# 23_LMS2_RX1_BB_ADC.net
KiCad netlist of a schematic drawn in Altium Designer
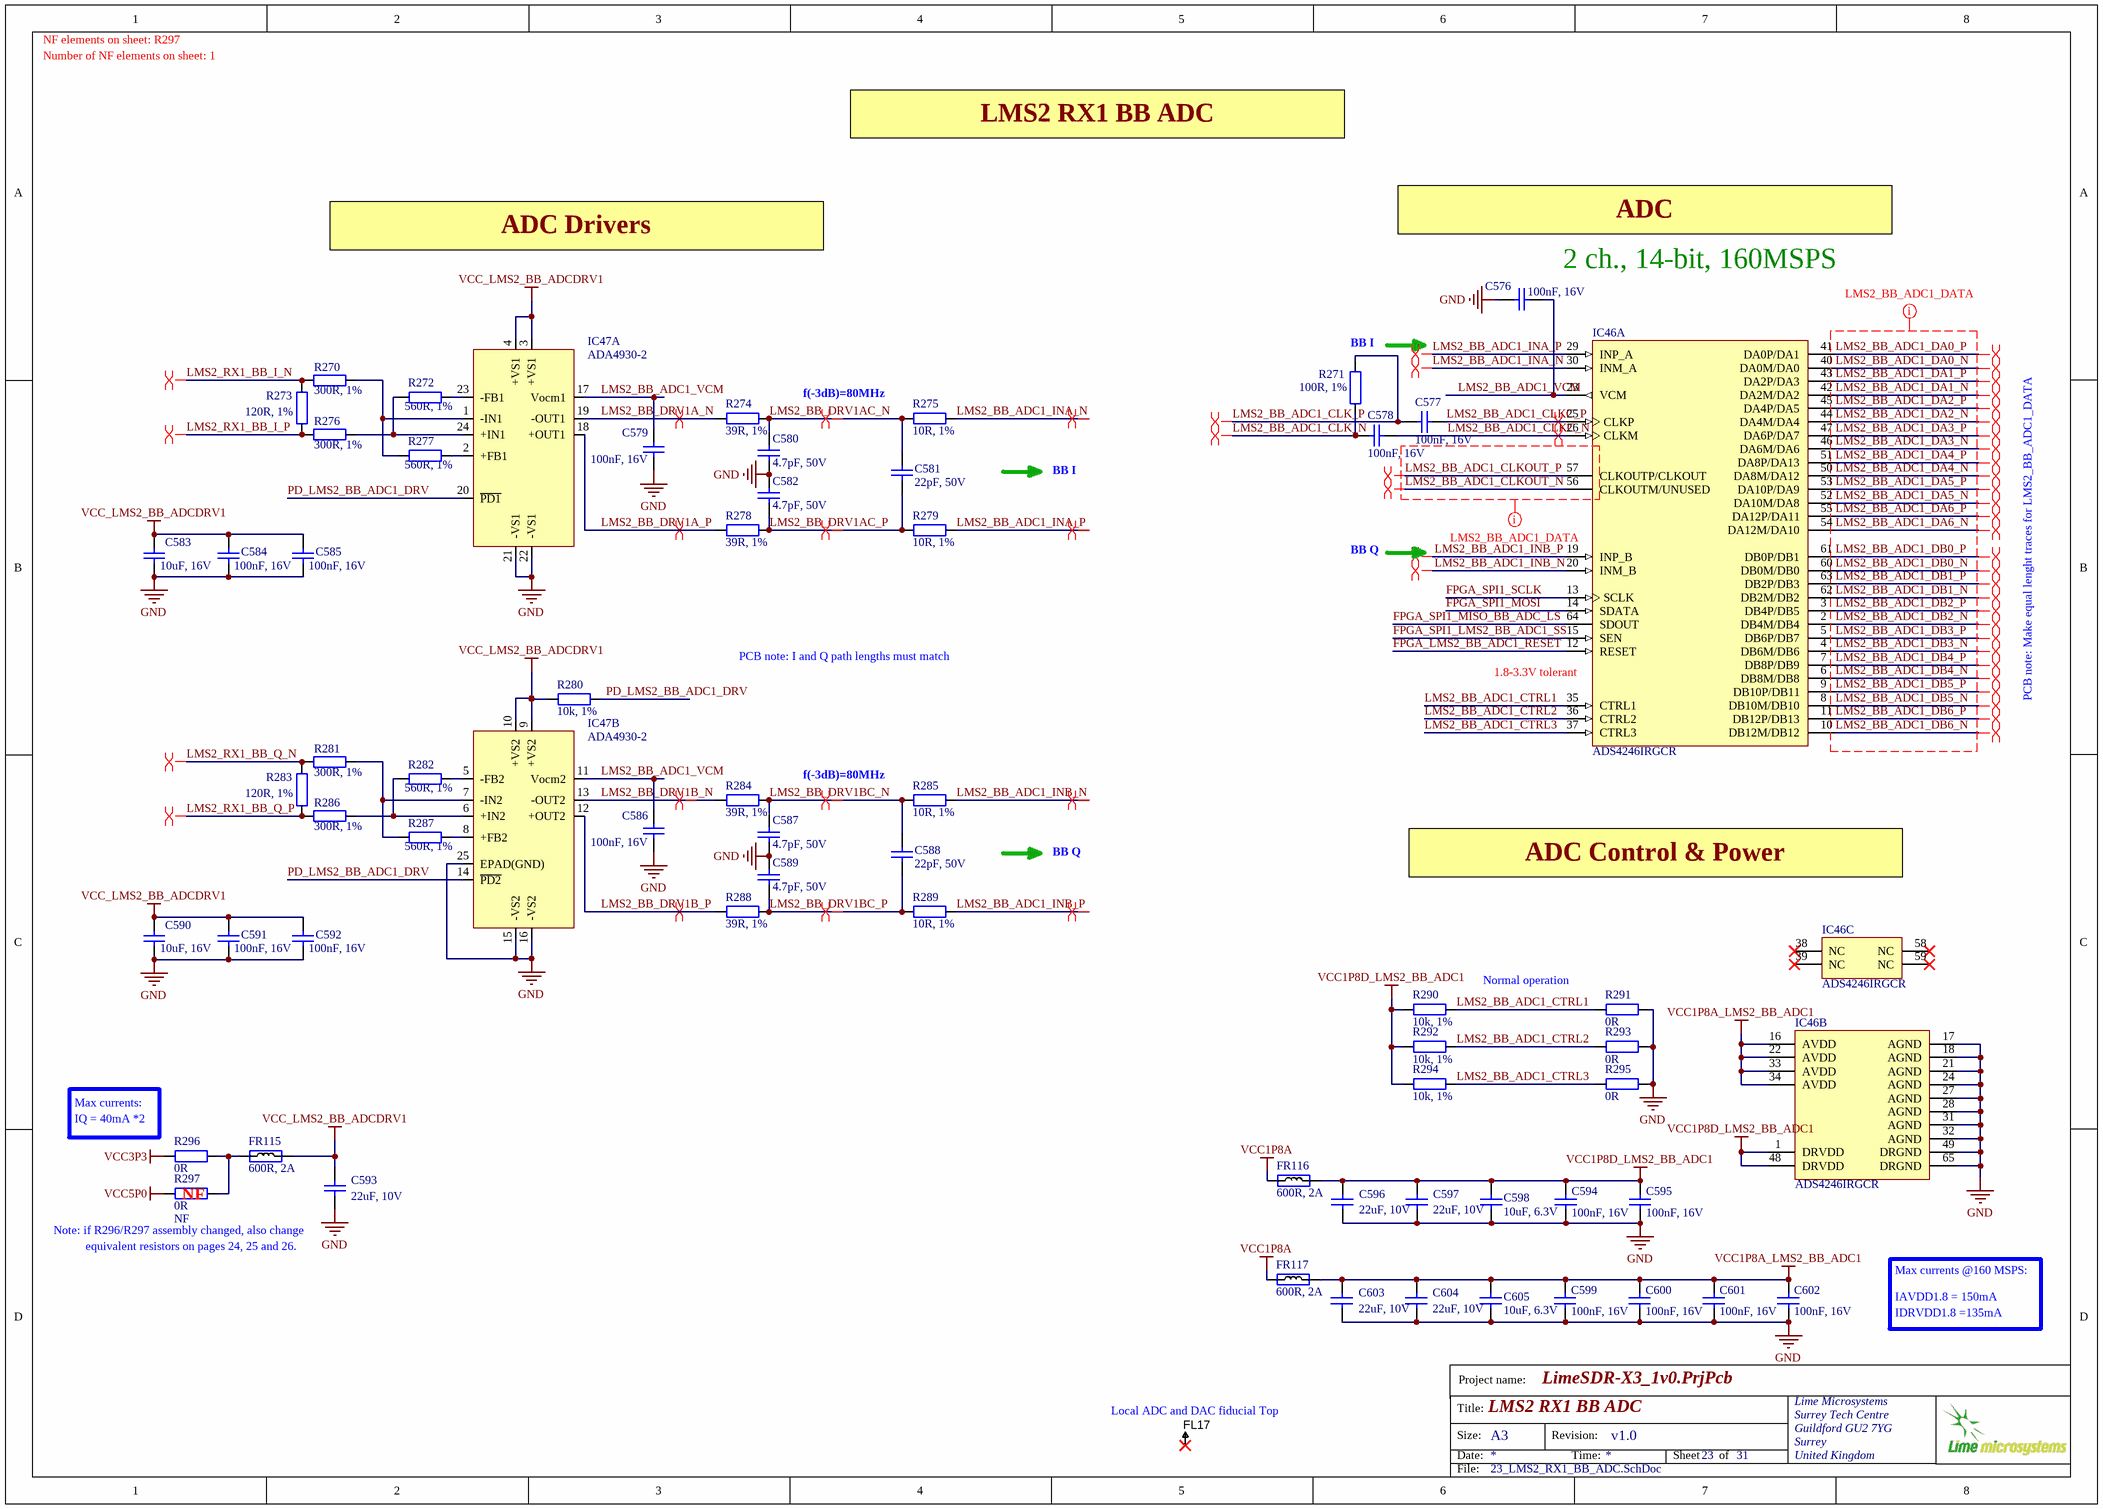
[diagram p0: 23_LMS2_RX1_BB_ADC.SchDoc]

(export (version "E")
  (design (tool "Eeschema 10.0.6"))
  (components
    (comp (ref "C576")
      (value "100nF, 16V")
      (footprint "CAP0402")
      (fields (field (name "TOLERANCE") "10 %") (field (name "MANUFACTURER") "Murata Electronics"))
      (libsource (lib "") (part "Cap_0603_3"))
    )
    (comp (ref "C577")
      (value "100nF, 16V")
      (footprint "CAP0402")
      (fields (field (name "TOLERANCE") "10 %") (field (name "MANUFACTURER") "Murata Electronics"))
      (libsource (lib "") (part "Cap_0603_3"))
    )
    (comp (ref "C578")
      (value "100nF, 16V")
      (footprint "CAP0402")
      (fields (field (name "TOLERANCE") "10 %") (field (name "MANUFACTURER") "Murata Electronics"))
      (libsource (lib "") (part "Cap_0603_4"))
    )
    (comp (ref "C579")
      (value "100nF, 16V")
      (footprint "CAP0402")
      (fields (field (name "TOLERANCE") "10 %") (field (name "MANUFACTURER") "Murata Electronics"))
      (libsource (lib "") (part "Cap_0603_4"))
    )
    (comp (ref "C580")
      (value "4.7pF, 50V")
      (footprint "CAP0402")
      (fields (field (name "MANUFACTURER") "MURATA"))
      (libsource (lib "") (part "Cap_0402_1"))
    )
    (comp (ref "C581")
      (value "22pF, 50V")
      (footprint "CAP0402")
      (fields (field (name "TOLERANCE") "±5%") (field (name "MANUFACTURER") "Yageo"))
      (libsource (lib "LimeMicroAltiumLib_schLib") (part "Cap_0402"))
    )
    (comp (ref "C582")
      (value "4.7pF, 50V")
      (footprint "CAP0402")
      (fields (field (name "MANUFACTURER") "MURATA"))
      (libsource (lib "") (part "Cap_0402_1"))
    )
    (comp (ref "C583")
      (value "10uF, 16V")
      (footprint "CAP0603")
      (fields (field (name "MANUFACTURER") "Yageo") (field (name "TOLERANCE") "±20%"))
      (libsource (lib "LimeMicroAltiumLib_schLib") (part "Cap_0603"))
    )
    (comp (ref "C584")
      (value "100nF, 16V")
      (footprint "CAP0402")
      (fields (field (name "TOLERANCE") "10 %") (field (name "MANUFACTURER") "Murata Electronics"))
      (libsource (lib "") (part "Cap_0603_4"))
    )
    (comp (ref "C585")
      (value "100nF, 16V")
      (footprint "CAP0402")
      (fields (field (name "TOLERANCE") "10 %") (field (name "MANUFACTURER") "Murata Electronics"))
      (libsource (lib "") (part "Cap_0603_4"))
    )
    (comp (ref "C586")
      (value "100nF, 16V")
      (footprint "CAP0402")
      (fields (field (name "TOLERANCE") "10 %") (field (name "MANUFACTURER") "Murata Electronics"))
      (libsource (lib "") (part "Cap_0603_5"))
    )
    (comp (ref "C587")
      (value "4.7pF, 50V")
      (footprint "CAP0402")
      (fields (field (name "MANUFACTURER") "MURATA"))
      (libsource (lib "") (part "Cap_0402_1"))
    )
    (comp (ref "C588")
      (value "22pF, 50V")
      (footprint "CAP0402")
      (fields (field (name "TOLERANCE") "±5%") (field (name "MANUFACTURER") "Yageo"))
      (libsource (lib "LimeMicroAltiumLib_schLib") (part "Cap_0402"))
    )
    (comp (ref "C589")
      (value "4.7pF, 50V")
      (footprint "CAP0402")
      (fields (field (name "MANUFACTURER") "MURATA"))
      (libsource (lib "") (part "Cap_0402_1"))
    )
    (comp (ref "C590")
      (value "10uF, 16V")
      (footprint "CAP0603")
      (fields (field (name "MANUFACTURER") "Yageo") (field (name "TOLERANCE") "±20%"))
      (libsource (lib "LimeMicroAltiumLib_schLib") (part "Cap_0603"))
    )
    (comp (ref "C591")
      (value "100nF, 16V")
      (footprint "CAP0402")
      (fields (field (name "TOLERANCE") "10 %") (field (name "MANUFACTURER") "Murata Electronics"))
      (libsource (lib "") (part "Cap_0603_4"))
    )
    (comp (ref "C592")
      (value "100nF, 16V")
      (footprint "CAP0402")
      (fields (field (name "TOLERANCE") "10 %") (field (name "MANUFACTURER") "Murata Electronics"))
      (libsource (lib "") (part "Cap_0603_4"))
    )
    (comp (ref "C593")
      (value "22uF, 10V")
      (footprint "CAP0603")
      (fields (field (name "TOLERANCE") "20 %") (field (name "MANUFACTURER") "TDK Corporation"))
      (libsource (lib "") (part "Cap_0603_6"))
    )
    (comp (ref "C594")
      (value "100nF, 16V")
      (footprint "CAP0402")
      (fields (field (name "TOLERANCE") "10 %") (field (name "MANUFACTURER") "Murata Electronics"))
      (libsource (lib "") (part "Cap_0603_1"))
    )
    (comp (ref "C595")
      (value "100nF, 16V")
      (footprint "CAP0402")
      (fields (field (name "TOLERANCE") "10 %") (field (name "MANUFACTURER") "Murata Electronics"))
      (libsource (lib "") (part "Cap_0603_1"))
    )
    (comp (ref "C596")
      (value "22uF, 10V")
      (footprint "CAP0603")
      (fields (field (name "TOLERANCE") "20 %") (field (name "MANUFACTURER") "TDK Corporation"))
      (libsource (lib "") (part "Cap_0603_1"))
    )
    (comp (ref "C597")
      (value "22uF, 10V")
      (footprint "CAP0603")
      (fields (field (name "TOLERANCE") "20 %") (field (name "MANUFACTURER") "TDK Corporation"))
      (libsource (lib "") (part "Cap_0603_1"))
    )
    (comp (ref "C598")
      (value "10uF, 6.3V")
      (footprint "CAP0603")
      (fields (field (name "TOLERANCE") "±20%") (field (name "MANUFACTURER") "Yageo"))
      (libsource (lib "") (part "Cap_0603_7"))
    )
    (comp (ref "C599")
      (value "100nF, 16V")
      (footprint "CAP0402")
      (fields (field (name "TOLERANCE") "10 %") (field (name "MANUFACTURER") "Murata Electronics"))
      (libsource (lib "LimeFPGAboard_schLib") (part "Cap_0603"))
    )
    (comp (ref "C600")
      (value "100nF, 16V")
      (footprint "CAP0402")
      (fields (field (name "TOLERANCE") "10 %") (field (name "MANUFACTURER") "Murata Electronics"))
      (libsource (lib "LimeFPGAboard_schLib") (part "Cap_0603"))
    )
    (comp (ref "C601")
      (value "100nF, 16V")
      (footprint "CAP0402")
      (fields (field (name "TOLERANCE") "10 %") (field (name "MANUFACTURER") "Murata Electronics"))
      (libsource (lib "LimeFPGAboard_schLib") (part "Cap_0603"))
    )
    (comp (ref "C602")
      (value "100nF, 16V")
      (footprint "CAP0402")
      (fields (field (name "TOLERANCE") "10 %") (field (name "MANUFACTURER") "Murata Electronics"))
      (libsource (lib "LimeFPGAboard_schLib") (part "Cap_0603"))
    )
    (comp (ref "C603")
      (value "22uF, 10V")
      (footprint "CAP0603")
      (fields (field (name "TOLERANCE") "20 %") (field (name "MANUFACTURER") "TDK Corporation"))
      (libsource (lib "LimeFPGAboard_schLib") (part "Cap_0603"))
    )
    (comp (ref "C604")
      (value "22uF, 10V")
      (footprint "CAP0603")
      (fields (field (name "TOLERANCE") "20 %") (field (name "MANUFACTURER") "TDK Corporation"))
      (libsource (lib "LimeFPGAboard_schLib") (part "Cap_0603"))
    )
    (comp (ref "C605")
      (value "10uF, 6.3V")
      (footprint "CAP0603")
      (fields (field (name "TOLERANCE") "±20%") (field (name "MANUFACTURER") "Yageo"))
      (libsource (lib "") (part "Cap_0603_2"))
    )
    (comp (ref "FL17")
      (value "Fiducial")
      (footprint "Fiducial_local")
      (libsource (lib "LimeMicroAltiumLib_schLib") (part "Fiducial"))
    )
    (comp (ref "FR115")
      (value "600R, 2A")
      (footprint "RES0805")
      (fields (field (name "MANUFACTURER") "TDK Corporation"))
      (libsource (lib "LimeMicroAltiumLib_schLib") (part "Ferrite"))
    )
    (comp (ref "FR116")
      (value "600R, 2A")
      (footprint "RES0805")
      (fields (field (name "MANUFACTURER") "TDK Corporation"))
      (libsource (lib "LimeFPGAboard_schLib") (part "Ferrite"))
    )
    (comp (ref "FR117")
      (value "600R, 2A")
      (footprint "RES0805")
      (fields (field (name "MANUFACTURER") "TDK Corporation"))
      (libsource (lib "LimeFPGAboard_schLib") (part "Ferrite"))
    )
    (comp (ref "IC46")
      (value "ADS4246IRGCR")
      (footprint "TI-RGC64-7400X7400TP_V")
      (description "14-Bit 160 MSPS Dual Low Power ADC, -40 to 85 degC, 64-pin QFN (RGC64), Green (RoHS & no Sb/Br)")
      (fields (field (name "MANUFACTURER") "Texas Instruments"))
      (libsource (lib "") (part "ADS4246IRGCR_1"))
    )
    (comp (ref "IC47")
      (value "ADA4930-2")
      (footprint "ADA4930-2_LFCSP-24")
      (fields (field (name "MANUFACTURER") "Analog Devices Inc."))
      (libsource (lib "") (part "ADA4930-2_1"))
    )
    (comp (ref "R270")
      (value "300R, 1%")
      (footprint "RES0402")
      (fields (field (name "TOLERANCE") "±1%") (field (name "MANUFACTURER") "Vishay Dale"))
      (libsource (lib "") (part "Res_0402_1"))
    )
    (comp (ref "R271")
      (value "100R, 1%")
      (footprint "RES0402")
      (fields (field (name "TOLERANCE") "±1%") (field (name "MANUFACTURER") "Stackpole Electronics Inc."))
      (libsource (lib "") (part "Res_0402_1"))
    )
    (comp (ref "R272")
      (value "560R, 1%")
      (footprint "RES0402")
      (fields (field (name "TOLERANCE") "±1%") (field (name "MANUFACTURER") "Vishay Dale"))
      (libsource (lib "") (part "Res_0402_1"))
    )
    (comp (ref "R273")
      (value "120R, 1%")
      (footprint "RES0402")
      (fields (field (name "MANUFACTURER") "Yageo") (field (name "TOLERANCE") "1%"))
      (libsource (lib "LimeFPGAboard_schLib") (part "Res_0402"))
    )
    (comp (ref "R274")
      (value "39R, 1%")
      (footprint "RES0402")
      (fields (field (name "MANUFACTURER") "Yageo") (field (name "TOLERANCE") "1%"))
      (libsource (lib "LimeMicroAltiumLib_schLib") (part "Res_0402"))
    )
    (comp (ref "R275")
      (value "10R, 1%")
      (footprint "RES0402")
      (fields (field (name "TOLERANCE") "1%"))
      (libsource (lib "LimeMicroAltiumLib_schLib") (part "Res_0402"))
    )
    (comp (ref "R276")
      (value "300R, 1%")
      (footprint "RES0402")
      (fields (field (name "TOLERANCE") "±1%") (field (name "MANUFACTURER") "Vishay Dale"))
      (libsource (lib "") (part "Res_0402_1"))
    )
    (comp (ref "R277")
      (value "560R, 1%")
      (footprint "RES0402")
      (fields (field (name "TOLERANCE") "±1%") (field (name "MANUFACTURER") "Vishay Dale"))
      (libsource (lib "") (part "Res_0402_1"))
    )
    (comp (ref "R278")
      (value "39R, 1%")
      (footprint "RES0402")
      (fields (field (name "MANUFACTURER") "Yageo") (field (name "TOLERANCE") "1%"))
      (libsource (lib "LimeMicroAltiumLib_schLib") (part "Res_0402"))
    )
    (comp (ref "R279")
      (value "10R, 1%")
      (footprint "RES0402")
      (fields (field (name "TOLERANCE") "1%"))
      (libsource (lib "LimeMicroAltiumLib_schLib") (part "Res_0402"))
    )
    (comp (ref "R280")
      (value "10k, 1%")
      (footprint "RES0402")
      (fields (field (name "MANUFACTURER") "Yageo") (field (name "TOLERANCE") "±1%"))
      (libsource (lib "LimeMicroAltiumLib_schLib") (part "Res_0402"))
    )
    (comp (ref "R281")
      (value "300R, 1%")
      (footprint "RES0402")
      (fields (field (name "TOLERANCE") "±1%") (field (name "MANUFACTURER") "Vishay Dale"))
      (libsource (lib "") (part "Res_0402_1"))
    )
    (comp (ref "R282")
      (value "560R, 1%")
      (footprint "RES0402")
      (fields (field (name "TOLERANCE") "±1%") (field (name "MANUFACTURER") "Vishay Dale"))
      (libsource (lib "") (part "Res_0402_1"))
    )
    (comp (ref "R283")
      (value "120R, 1%")
      (footprint "RES0402")
      (fields (field (name "MANUFACTURER") "Yageo") (field (name "TOLERANCE") "1%"))
      (libsource (lib "LimeFPGAboard_schLib") (part "Res_0402"))
    )
    (comp (ref "R284")
      (value "39R, 1%")
      (footprint "RES0402")
      (fields (field (name "MANUFACTURER") "Yageo") (field (name "TOLERANCE") "1%"))
      (libsource (lib "LimeMicroAltiumLib_schLib") (part "Res_0402"))
    )
    (comp (ref "R285")
      (value "10R, 1%")
      (footprint "RES0402")
      (fields (field (name "TOLERANCE") "1%"))
      (libsource (lib "LimeMicroAltiumLib_schLib") (part "Res_0402"))
    )
    (comp (ref "R286")
      (value "300R, 1%")
      (footprint "RES0402")
      (fields (field (name "TOLERANCE") "±1%") (field (name "MANUFACTURER") "Vishay Dale"))
      (libsource (lib "") (part "Res_0402_1"))
    )
    (comp (ref "R287")
      (value "560R, 1%")
      (footprint "RES0402")
      (fields (field (name "TOLERANCE") "±1%") (field (name "MANUFACTURER") "Vishay Dale"))
      (libsource (lib "") (part "Res_0402_1"))
    )
    (comp (ref "R288")
      (value "39R, 1%")
      (footprint "RES0402")
      (fields (field (name "MANUFACTURER") "Yageo") (field (name "TOLERANCE") "1%"))
      (libsource (lib "LimeMicroAltiumLib_schLib") (part "Res_0402"))
    )
    (comp (ref "R289")
      (value "10R, 1%")
      (footprint "RES0402")
      (fields (field (name "TOLERANCE") "1%"))
      (libsource (lib "LimeMicroAltiumLib_schLib") (part "Res_0402"))
    )
    (comp (ref "R290")
      (value "10k, 1%")
      (footprint "RES0402")
      (fields (field (name "MANUFACTURER") "Yageo") (field (name "TOLERANCE") "±1%"))
      (libsource (lib "LimeMicroAltiumLib_schLib") (part "Res_0402"))
    )
    (comp (ref "R291")
      (value "0R")
      (footprint "RES0402")
      (fields (field (name "MANUFACTURER") "Yageo"))
      (libsource (lib "") (part "Res_0402_1"))
    )
    (comp (ref "R292")
      (value "10k, 1%")
      (footprint "RES0402")
      (fields (field (name "MANUFACTURER") "Yageo") (field (name "TOLERANCE") "±1%"))
      (libsource (lib "LimeMicroAltiumLib_schLib") (part "Res_0402"))
    )
    (comp (ref "R293")
      (value "0R")
      (footprint "RES0402")
      (fields (field (name "MANUFACTURER") "Yageo"))
      (libsource (lib "") (part "Res_0402_1"))
    )
    (comp (ref "R294")
      (value "10k, 1%")
      (footprint "RES0402")
      (fields (field (name "MANUFACTURER") "Yageo") (field (name "TOLERANCE") "±1%"))
      (libsource (lib "LimeMicroAltiumLib_schLib") (part "Res_0402"))
    )
    (comp (ref "R295")
      (value "0R")
      (footprint "RES0402")
      (fields (field (name "MANUFACTURER") "Yageo"))
      (libsource (lib "") (part "Res_0402_1"))
    )
    (comp (ref "R296")
      (value "0R")
      (footprint "RES0402")
      (fields (field (name "MANUFACTURER") "Yageo") (field (name "TOLERANCE") "Jumper"))
      (libsource (lib "LimeMicroAltiumLib_schLib") (part "Res_0402"))
    )
    (comp (ref "R297")
      (value "0R")
      (footprint "RES0402")
      (fields
        (field (name "ASSEMBLY INFO") "NF")
        (field (name "MANUFACTURER") "Yageo")
        (field (name "TOLERANCE") "Jumper")
      )
      (libsource (lib "LimeMicroAltiumLib_schLib") (part "Res_0402"))
    )
  )
  (nets
    (net (code "1") (name "/FPGA_LMS2_BB_ADC1_RESET") (class "Default")
      (node (ref "IC46") (pin "12") (pinfunction "RESET_12") (pintype "input"))
    )
    (net (code "2") (name "/FPGA_SPI1_LMS2_BB_ADC1_SS") (class "Default")
      (node (ref "IC46") (pin "15") (pinfunction "SEN_15") (pintype "input"))
    )
    (net (code "3") (name "/FPGA_SPI1_MISO_BB_ADC_LS") (class "Default")
      (node (ref "IC46") (pin "64") (pinfunction "SDOUT_64") (pintype "tri_state"))
    )
    (net (code "4") (name "/FPGA_SPI1_MOSI") (class "Default")
      (node (ref "IC46") (pin "14") (pinfunction "SDATA_14") (pintype "input"))
    )
    (net (code "5") (name "/FPGA_SPI1_SCLK") (class "Default")
      (node (ref "IC46") (pin "13") (pinfunction "SCLK_13") (pintype "input"))
    )
    (net (code "6") (name "/LMS2_BB_ADC1_CLKC_N") (class "Default")
      (node (ref "C578") (pin "1") (pinfunction "1_1") (pintype "passive"))
      (node (ref "IC46") (pin "26") (pinfunction "CLKM_26") (pintype "input"))
    )
    (net (code "7") (name "/LMS2_BB_ADC1_CLKC_P") (class "Default")
      (node (ref "C577") (pin "1") (pinfunction "1_1") (pintype "passive"))
      (node (ref "IC46") (pin "25") (pinfunction "CLKP_25") (pintype "input"))
    )
    (net (code "8") (name "/LMS2_BB_ADC1_CLKOUT_N") (class "Default")
      (node (ref "IC46") (pin "56") (pinfunction "CLKOUTM/UNUSED_56") (pintype "tri_state"))
    )
    (net (code "9") (name "/LMS2_BB_ADC1_CLKOUT_P") (class "Default")
      (node (ref "IC46") (pin "57") (pinfunction "CLKOUTP/CLKOUT_57") (pintype "tri_state"))
    )
    (net (code "10") (name "/LMS2_BB_ADC1_CLK_N") (class "Default")
      (node (ref "C578") (pin "2") (pinfunction "2_2") (pintype "passive"))
      (node (ref "R271") (pin "1") (pinfunction "1_1") (pintype "passive"))
    )
    (net (code "11") (name "/LMS2_BB_ADC1_CLK_P") (class "Default")
      (node (ref "C577") (pin "2") (pinfunction "2_2") (pintype "passive"))
      (node (ref "R271") (pin "2") (pinfunction "2_2") (pintype "passive"))
    )
    (net (code "12") (name "/LMS2_BB_ADC1_CTRL1") (class "Default")
      (node (ref "IC46") (pin "35") (pinfunction "CTRL1_35") (pintype "input"))
      (node (ref "R290") (pin "1") (pinfunction "1_1") (pintype "passive"))
      (node (ref "R291") (pin "2") (pinfunction "2_2") (pintype "passive"))
    )
    (net (code "13") (name "/LMS2_BB_ADC1_CTRL2") (class "Default")
      (node (ref "IC46") (pin "36") (pinfunction "CTRL2_36") (pintype "input"))
      (node (ref "R292") (pin "1") (pinfunction "1_1") (pintype "passive"))
      (node (ref "R293") (pin "2") (pinfunction "2_2") (pintype "passive"))
    )
    (net (code "14") (name "/LMS2_BB_ADC1_CTRL3") (class "Default")
      (node (ref "IC46") (pin "37") (pinfunction "CTRL3_37") (pintype "input"))
      (node (ref "R294") (pin "1") (pinfunction "1_1") (pintype "passive"))
      (node (ref "R295") (pin "2") (pinfunction "2_2") (pintype "passive"))
    )
    (net (code "15") (name "/LMS2_BB_ADC1_DA0_N") (class "Default")
      (node (ref "IC46") (pin "40") (pinfunction "DA0M/DA0_40") (pintype "tri_state"))
    )
    (net (code "16") (name "/LMS2_BB_ADC1_DA0_P") (class "Default")
      (node (ref "IC46") (pin "41") (pinfunction "DA0P/DA1_41") (pintype "tri_state"))
    )
    (net (code "17") (name "/LMS2_BB_ADC1_DA1_N") (class "Default")
      (node (ref "IC46") (pin "42") (pinfunction "DA2M/DA2_42") (pintype "tri_state"))
    )
    (net (code "18") (name "/LMS2_BB_ADC1_DA1_P") (class "Default")
      (node (ref "IC46") (pin "43") (pinfunction "DA2P/DA3_43") (pintype "tri_state"))
    )
    (net (code "19") (name "/LMS2_BB_ADC1_DA2_N") (class "Default")
      (node (ref "IC46") (pin "44") (pinfunction "DA4M/DA4_44") (pintype "tri_state"))
    )
    (net (code "20") (name "/LMS2_BB_ADC1_DA2_P") (class "Default")
      (node (ref "IC46") (pin "45") (pinfunction "DA4P/DA5_45") (pintype "tri_state"))
    )
    (net (code "21") (name "/LMS2_BB_ADC1_DA3_N") (class "Default")
      (node (ref "IC46") (pin "46") (pinfunction "DA6M/DA6_46") (pintype "tri_state"))
    )
    (net (code "22") (name "/LMS2_BB_ADC1_DA3_P") (class "Default")
      (node (ref "IC46") (pin "47") (pinfunction "DA6P/DA7_47") (pintype "tri_state"))
    )
    (net (code "23") (name "/LMS2_BB_ADC1_DA4_N") (class "Default")
      (node (ref "IC46") (pin "50") (pinfunction "DA8M/DA12_50") (pintype "tri_state"))
    )
    (net (code "24") (name "/LMS2_BB_ADC1_DA4_P") (class "Default")
      (node (ref "IC46") (pin "51") (pinfunction "DA8P/DA13_51") (pintype "tri_state"))
    )
    (net (code "25") (name "/LMS2_BB_ADC1_DA5_N") (class "Default")
      (node (ref "IC46") (pin "52") (pinfunction "DA10M/DA8_52") (pintype "tri_state"))
    )
    (net (code "26") (name "/LMS2_BB_ADC1_DA5_P") (class "Default")
      (node (ref "IC46") (pin "53") (pinfunction "DA10P/DA9_53") (pintype "tri_state"))
    )
    (net (code "27") (name "/LMS2_BB_ADC1_DA6_N") (class "Default")
      (node (ref "IC46") (pin "54") (pinfunction "DA12M/DA10_54") (pintype "tri_state"))
    )
    (net (code "28") (name "/LMS2_BB_ADC1_DA6_P") (class "Default")
      (node (ref "IC46") (pin "55") (pinfunction "DA12P/DA11_55") (pintype "tri_state"))
    )
    (net (code "29") (name "/LMS2_BB_ADC1_DB0_N") (class "Default")
      (node (ref "IC46") (pin "60") (pinfunction "DB0M/DB0_60") (pintype "tri_state"))
    )
    (net (code "30") (name "/LMS2_BB_ADC1_DB0_P") (class "Default")
      (node (ref "IC46") (pin "61") (pinfunction "DB0P/DB1_61") (pintype "tri_state"))
    )
    (net (code "31") (name "/LMS2_BB_ADC1_DB1_N") (class "Default")
      (node (ref "IC46") (pin "62") (pinfunction "DB2M/DB2_62") (pintype "tri_state"))
    )
    (net (code "32") (name "/LMS2_BB_ADC1_DB1_P") (class "Default")
      (node (ref "IC46") (pin "63") (pinfunction "DB2P/DB3_63") (pintype "tri_state"))
    )
    (net (code "33") (name "/LMS2_BB_ADC1_DB2_N") (class "Default")
      (node (ref "IC46") (pin "2") (pinfunction "DB4M/DB4_2") (pintype "tri_state"))
    )
    (net (code "34") (name "/LMS2_BB_ADC1_DB2_P") (class "Default")
      (node (ref "IC46") (pin "3") (pinfunction "DB4P/DB5_3") (pintype "tri_state"))
    )
    (net (code "35") (name "/LMS2_BB_ADC1_DB3_N") (class "Default")
      (node (ref "IC46") (pin "4") (pinfunction "DB6M/DB6_4") (pintype "tri_state"))
    )
    (net (code "36") (name "/LMS2_BB_ADC1_DB3_P") (class "Default")
      (node (ref "IC46") (pin "5") (pinfunction "DB6P/DB7_5") (pintype "tri_state"))
    )
    (net (code "37") (name "/LMS2_BB_ADC1_DB4_N") (class "Default")
      (node (ref "IC46") (pin "6") (pinfunction "DB8M/DB8_6") (pintype "tri_state"))
    )
    (net (code "38") (name "/LMS2_BB_ADC1_DB4_P") (class "Default")
      (node (ref "IC46") (pin "7") (pinfunction "DB8P/DB9_7") (pintype "tri_state"))
    )
    (net (code "39") (name "/LMS2_BB_ADC1_DB5_N") (class "Default")
      (node (ref "IC46") (pin "8") (pinfunction "DB10M/DB10_8") (pintype "tri_state"))
    )
    (net (code "40") (name "/LMS2_BB_ADC1_DB5_P") (class "Default")
      (node (ref "IC46") (pin "9") (pinfunction "DB10P/DB11_9") (pintype "tri_state"))
    )
    (net (code "41") (name "/LMS2_BB_ADC1_DB6_N") (class "Default")
      (node (ref "IC46") (pin "10") (pinfunction "DB12M/DB12_10") (pintype "tri_state"))
    )
    (net (code "42") (name "/LMS2_BB_ADC1_DB6_P") (class "Default")
      (node (ref "IC46") (pin "11") (pinfunction "DB12P/DB13_11") (pintype "tri_state"))
    )
    (net (code "43") (name "/LMS2_BB_ADC1_INA_N") (class "Default")
      (node (ref "IC46") (pin "30") (pinfunction "INM_A_30") (pintype "input"))
      (node (ref "R275") (pin "1") (pinfunction "1_1") (pintype "passive"))
    )
    (net (code "44") (name "/LMS2_BB_ADC1_INA_P") (class "Default")
      (node (ref "IC46") (pin "29") (pinfunction "INP_A_29") (pintype "input"))
      (node (ref "R279") (pin "1") (pinfunction "1_1") (pintype "passive"))
    )
    (net (code "45") (name "/LMS2_BB_ADC1_INB_N") (class "Default")
      (node (ref "IC46") (pin "20") (pinfunction "INM_B_20") (pintype "input"))
      (node (ref "R285") (pin "1") (pinfunction "1_1") (pintype "passive"))
    )
    (net (code "46") (name "/LMS2_BB_ADC1_INB_P") (class "Default")
      (node (ref "IC46") (pin "19") (pinfunction "INP_B_19") (pintype "input"))
      (node (ref "R289") (pin "1") (pinfunction "1_1") (pintype "passive"))
    )
    (net (code "47") (name "/LMS2_BB_ADC1_VCM") (class "Default")
      (node (ref "C576") (pin "2") (pinfunction "2_2") (pintype "passive"))
      (node (ref "C579") (pin "1") (pinfunction "1_1") (pintype "passive"))
      (node (ref "C586") (pin "1") (pinfunction "1_1") (pintype "passive"))
      (node (ref "IC46") (pin "23") (pinfunction "VCM_23") (pintype "output"))
      (node (ref "IC47") (pin "11") (pinfunction "Vocm2_11") (pintype "input"))
      (node (ref "IC47") (pin "17") (pinfunction "Vocm1_17") (pintype "input"))
    )
    (net (code "48") (name "/LMS2_BB_DRV1AC_N") (class "Default")
      (node (ref "C580") (pin "1") (pinfunction "1_1") (pintype "passive"))
      (node (ref "C581") (pin "1") (pinfunction "1_1") (pintype "passive"))
      (node (ref "R274") (pin "1") (pinfunction "1_1") (pintype "passive"))
      (node (ref "R275") (pin "2") (pinfunction "2_2") (pintype "passive"))
    )
    (net (code "49") (name "/LMS2_BB_DRV1AC_P") (class "Default")
      (node (ref "C581") (pin "2") (pinfunction "2_2") (pintype "passive"))
      (node (ref "C582") (pin "2") (pinfunction "2_2") (pintype "passive"))
      (node (ref "R278") (pin "1") (pinfunction "1_1") (pintype "passive"))
      (node (ref "R279") (pin "2") (pinfunction "2_2") (pintype "passive"))
    )
    (net (code "50") (name "/LMS2_BB_DRV1A_N") (class "Default")
      (node (ref "IC47") (pin "19") (pinfunction "-OUT1_19") (pintype "output"))
      (node (ref "R274") (pin "2") (pinfunction "2_2") (pintype "passive"))
    )
    (net (code "51") (name "/LMS2_BB_DRV1A_P") (class "Default")
      (node (ref "IC47") (pin "18") (pinfunction "+OUT1_18") (pintype "output"))
      (node (ref "R278") (pin "2") (pinfunction "2_2") (pintype "passive"))
    )
    (net (code "52") (name "/LMS2_BB_DRV1BC_N") (class "Default")
      (node (ref "C587") (pin "1") (pinfunction "1_1") (pintype "passive"))
      (node (ref "C588") (pin "1") (pinfunction "1_1") (pintype "passive"))
      (node (ref "R284") (pin "1") (pinfunction "1_1") (pintype "passive"))
      (node (ref "R285") (pin "2") (pinfunction "2_2") (pintype "passive"))
    )
    (net (code "53") (name "/LMS2_BB_DRV1BC_P") (class "Default")
      (node (ref "C588") (pin "2") (pinfunction "2_2") (pintype "passive"))
      (node (ref "C589") (pin "2") (pinfunction "2_2") (pintype "passive"))
      (node (ref "R288") (pin "1") (pinfunction "1_1") (pintype "passive"))
      (node (ref "R289") (pin "2") (pinfunction "2_2") (pintype "passive"))
    )
    (net (code "54") (name "/LMS2_BB_DRV1B_N") (class "Default")
      (node (ref "IC47") (pin "13") (pinfunction "-OUT2_13") (pintype "output"))
      (node (ref "R284") (pin "2") (pinfunction "2_2") (pintype "passive"))
    )
    (net (code "55") (name "/LMS2_BB_DRV1B_P") (class "Default")
      (node (ref "IC47") (pin "12") (pinfunction "+OUT2_12") (pintype "output"))
      (node (ref "R288") (pin "2") (pinfunction "2_2") (pintype "passive"))
    )
    (net (code "56") (name "/LMS2_RX1_BB_I_N") (class "Default")
      (node (ref "R270") (pin "2") (pinfunction "2_2") (pintype "passive"))
      (node (ref "R273") (pin "2") (pinfunction "2_2") (pintype "passive"))
    )
    (net (code "57") (name "/LMS2_RX1_BB_I_P") (class "Default")
      (node (ref "R273") (pin "1") (pinfunction "1_1") (pintype "passive"))
      (node (ref "R276") (pin "2") (pinfunction "2_2") (pintype "passive"))
    )
    (net (code "58") (name "/LMS2_RX1_BB_Q_N") (class "Default")
      (node (ref "R281") (pin "2") (pinfunction "2_2") (pintype "passive"))
      (node (ref "R283") (pin "2") (pinfunction "2_2") (pintype "passive"))
    )
    (net (code "59") (name "/LMS2_RX1_BB_Q_P") (class "Default")
      (node (ref "R283") (pin "1") (pinfunction "1_1") (pintype "passive"))
      (node (ref "R286") (pin "2") (pinfunction "2_2") (pintype "passive"))
    )
    (net (code "60") (name "/PD_LMS2_BB_ADC1_DRV") (class "Default")
      (node (ref "IC47") (pin "14") (pinfunction "~{PD2}_14") (pintype "input"))
      (node (ref "IC47") (pin "20") (pinfunction "~{PD1}_20") (pintype "input"))
      (node (ref "R280") (pin "1") (pinfunction "1_1") (pintype "passive"))
    )
    (net (code "61") (name "GND") (class "Default")
      (node (ref "C576") (pin "1") (pinfunction "1_1") (pintype "passive"))
      (node (ref "C579") (pin "2") (pinfunction "2_2") (pintype "passive"))
      (node (ref "C580") (pin "2") (pinfunction "2_2") (pintype "passive"))
      (node (ref "C582") (pin "1") (pinfunction "1_1") (pintype "passive"))
      (node (ref "C583") (pin "1") (pinfunction "1_1") (pintype "passive"))
      (node (ref "C584") (pin "2") (pinfunction "2_2") (pintype "passive"))
      (node (ref "C585") (pin "2") (pinfunction "2_2") (pintype "passive"))
      (node (ref "C586") (pin "2") (pinfunction "2_2") (pintype "passive"))
      (node (ref "C587") (pin "2") (pinfunction "2_2") (pintype "passive"))
      (node (ref "C589") (pin "1") (pinfunction "1_1") (pintype "passive"))
      (node (ref "C590") (pin "1") (pinfunction "1_1") (pintype "passive"))
      (node (ref "C591") (pin "2") (pinfunction "2_2") (pintype "passive"))
      (node (ref "C592") (pin "2") (pinfunction "2_2") (pintype "passive"))
      (node (ref "C593") (pin "1") (pinfunction "1_1") (pintype "passive"))
      (node (ref "C594") (pin "1") (pinfunction "1_1") (pintype "passive"))
      (node (ref "C595") (pin "1") (pinfunction "1_1") (pintype "passive"))
      (node (ref "C596") (pin "1") (pinfunction "1_1") (pintype "passive"))
      (node (ref "C597") (pin "1") (pinfunction "1_1") (pintype "passive"))
      (node (ref "C598") (pin "2") (pinfunction "2_2") (pintype "passive"))
      (node (ref "C599") (pin "1") (pinfunction "1_1") (pintype "passive"))
      (node (ref "C600") (pin "1") (pinfunction "1_1") (pintype "passive"))
      (node (ref "C601") (pin "1") (pinfunction "1_1") (pintype "passive"))
      (node (ref "C602") (pin "1") (pinfunction "1_1") (pintype "passive"))
      (node (ref "C603") (pin "1") (pinfunction "1_1") (pintype "passive"))
      (node (ref "C604") (pin "1") (pinfunction "1_1") (pintype "passive"))
      (node (ref "C605") (pin "2") (pinfunction "2_2") (pintype "passive"))
      (node (ref "IC46") (pin "17") (pinfunction "AGND_17") (pintype "power_in"))
      (node (ref "IC46") (pin "18") (pinfunction "AGND_18") (pintype "power_in"))
      (node (ref "IC46") (pin "21") (pinfunction "AGND_21") (pintype "power_in"))
      (node (ref "IC46") (pin "24") (pinfunction "AGND_24") (pintype "power_in"))
      (node (ref "IC46") (pin "27") (pinfunction "AGND_27") (pintype "power_in"))
      (node (ref "IC46") (pin "28") (pinfunction "AGND_28") (pintype "power_in"))
      (node (ref "IC46") (pin "31") (pinfunction "AGND_31") (pintype "power_in"))
      (node (ref "IC46") (pin "32") (pinfunction "AGND_32") (pintype "power_in"))
      (node (ref "IC46") (pin "49") (pinfunction "DRGND_49") (pintype "power_in"))
      (node (ref "IC46") (pin "65") (pinfunction "DRGND_65") (pintype "power_in"))
      (node (ref "IC47") (pin "15") (pinfunction "-VS2_15") (pintype "power_in"))
      (node (ref "IC47") (pin "16") (pinfunction "-VS2_16") (pintype "power_in"))
      (node (ref "IC47") (pin "21") (pinfunction "-VS1_21") (pintype "power_in"))
      (node (ref "IC47") (pin "22") (pinfunction "-VS1_22") (pintype "power_in"))
      (node (ref "IC47") (pin "25") (pinfunction "EPAD(GND)_25") (pintype "passive"))
      (node (ref "R291") (pin "1") (pinfunction "1_1") (pintype "passive"))
      (node (ref "R293") (pin "1") (pinfunction "1_1") (pintype "passive"))
      (node (ref "R295") (pin "1") (pinfunction "1_1") (pintype "passive"))
    )
    (net (code "62") (name "Net-(FR115-Pad1)") (class "Default")
      (node (ref "FR115") (pin "1") (pinfunction "1_1") (pintype "passive"))
      (node (ref "R296") (pin "1") (pinfunction "1_1") (pintype "passive"))
      (node (ref "R297") (pin "1") (pinfunction "1_1") (pintype "passive"))
    )
    (net (code "63") (name "Net-(IC47A-+FB1)") (class "Default")
      (node (ref "IC47") (pin "2") (pinfunction "+FB1_2") (pintype "output"))
      (node (ref "R277") (pin "1") (pinfunction "1_1") (pintype "passive"))
    )
    (net (code "64") (name "Net-(IC47A-+IN1)") (class "Default")
      (node (ref "IC47") (pin "24") (pinfunction "+IN1_24") (pintype "input"))
      (node (ref "R272") (pin "2") (pinfunction "2_2") (pintype "passive"))
      (node (ref "R276") (pin "1") (pinfunction "1_1") (pintype "passive"))
    )
    (net (code "65") (name "Net-(IC47A--FB1)") (class "Default")
      (node (ref "IC47") (pin "23") (pinfunction "-FB1_23") (pintype "output"))
      (node (ref "R272") (pin "1") (pinfunction "1_1") (pintype "passive"))
    )
    (net (code "66") (name "Net-(IC47A--IN1)") (class "Default")
      (node (ref "IC47") (pin "1") (pinfunction "-IN1_1") (pintype "input"))
      (node (ref "R270") (pin "1") (pinfunction "1_1") (pintype "passive"))
      (node (ref "R277") (pin "2") (pinfunction "2_2") (pintype "passive"))
    )
    (net (code "67") (name "Net-(IC47B-+FB2)") (class "Default")
      (node (ref "IC47") (pin "8") (pinfunction "+FB2_8") (pintype "output"))
      (node (ref "R287") (pin "1") (pinfunction "1_1") (pintype "passive"))
    )
    (net (code "68") (name "Net-(IC47B-+IN2)") (class "Default")
      (node (ref "IC47") (pin "6") (pinfunction "+IN2_6") (pintype "input"))
      (node (ref "R282") (pin "2") (pinfunction "2_2") (pintype "passive"))
      (node (ref "R286") (pin "1") (pinfunction "1_1") (pintype "passive"))
    )
    (net (code "69") (name "Net-(IC47B--FB2)") (class "Default")
      (node (ref "IC47") (pin "5") (pinfunction "-FB2_5") (pintype "output"))
      (node (ref "R282") (pin "1") (pinfunction "1_1") (pintype "passive"))
    )
    (net (code "70") (name "Net-(IC47B--IN2)") (class "Default")
      (node (ref "IC47") (pin "7") (pinfunction "-IN2_7") (pintype "input"))
      (node (ref "R281") (pin "1") (pinfunction "1_1") (pintype "passive"))
      (node (ref "R287") (pin "2") (pinfunction "2_2") (pintype "passive"))
    )
    (net (code "71") (name "VCC1P8A") (class "Default")
      (node (ref "FR116") (pin "1") (pinfunction "1_1") (pintype "passive"))
      (node (ref "FR117") (pin "1") (pinfunction "1_1") (pintype "passive"))
    )
    (net (code "72") (name "VCC1P8A_LMS2_BB_ADC1") (class "Default")
      (node (ref "C599") (pin "2") (pinfunction "2_2") (pintype "passive"))
      (node (ref "C600") (pin "2") (pinfunction "2_2") (pintype "passive"))
      (node (ref "C601") (pin "2") (pinfunction "2_2") (pintype "passive"))
      (node (ref "C602") (pin "2") (pinfunction "2_2") (pintype "passive"))
      (node (ref "C603") (pin "2") (pinfunction "2_2") (pintype "passive"))
      (node (ref "C604") (pin "2") (pinfunction "2_2") (pintype "passive"))
      (node (ref "C605") (pin "1") (pinfunction "1_1") (pintype "passive"))
      (node (ref "FR117") (pin "2") (pinfunction "2_2") (pintype "passive"))
      (node (ref "IC46") (pin "16") (pinfunction "AVDD_16") (pintype "power_in"))
      (node (ref "IC46") (pin "22") (pinfunction "AVDD_22") (pintype "power_in"))
      (node (ref "IC46") (pin "33") (pinfunction "AVDD_33") (pintype "power_in"))
      (node (ref "IC46") (pin "34") (pinfunction "AVDD_34") (pintype "power_in"))
    )
    (net (code "73") (name "VCC1P8D_LMS2_BB_ADC1") (class "Default")
      (node (ref "C594") (pin "2") (pinfunction "2_2") (pintype "passive"))
      (node (ref "C595") (pin "2") (pinfunction "2_2") (pintype "passive"))
      (node (ref "C596") (pin "2") (pinfunction "2_2") (pintype "passive"))
      (node (ref "C597") (pin "2") (pinfunction "2_2") (pintype "passive"))
      (node (ref "C598") (pin "1") (pinfunction "1_1") (pintype "passive"))
      (node (ref "FR116") (pin "2") (pinfunction "2_2") (pintype "passive"))
      (node (ref "IC46") (pin "1") (pinfunction "DRVDD_1") (pintype "power_in"))
      (node (ref "IC46") (pin "48") (pinfunction "DRVDD_48") (pintype "power_in"))
      (node (ref "R290") (pin "2") (pinfunction "2_2") (pintype "passive"))
      (node (ref "R292") (pin "2") (pinfunction "2_2") (pintype "passive"))
      (node (ref "R294") (pin "2") (pinfunction "2_2") (pintype "passive"))
    )
    (net (code "74") (name "VCC3P3") (class "Default")
      (node (ref "R296") (pin "2") (pinfunction "2_2") (pintype "passive"))
    )
    (net (code "75") (name "VCC5P0") (class "Default")
      (node (ref "R297") (pin "2") (pinfunction "2_2") (pintype "passive"))
    )
    (net (code "76") (name "VCC_LMS2_BB_ADCDRV1") (class "Default")
      (node (ref "C583") (pin "2") (pinfunction "2_2") (pintype "passive"))
      (node (ref "C584") (pin "1") (pinfunction "1_1") (pintype "passive"))
      (node (ref "C585") (pin "1") (pinfunction "1_1") (pintype "passive"))
      (node (ref "C590") (pin "2") (pinfunction "2_2") (pintype "passive"))
      (node (ref "C591") (pin "1") (pinfunction "1_1") (pintype "passive"))
      (node (ref "C592") (pin "1") (pinfunction "1_1") (pintype "passive"))
      (node (ref "C593") (pin "2") (pinfunction "2_2") (pintype "passive"))
      (node (ref "FR115") (pin "2") (pinfunction "2_2") (pintype "passive"))
      (node (ref "IC47") (pin "10") (pinfunction "+VS2_10") (pintype "power_in"))
      (node (ref "IC47") (pin "3") (pinfunction "+VS1_3") (pintype "power_in"))
      (node (ref "IC47") (pin "4") (pinfunction "+VS1_4") (pintype "power_in"))
      (node (ref "IC47") (pin "9") (pinfunction "+VS2_9") (pintype "power_in"))
      (node (ref "R280") (pin "2") (pinfunction "2_2") (pintype "passive"))
    )
    (net (code "77") (name "unconnected-(FL17-Pad1)") (class "Default")
      (node (ref "FL17") (pin "1") (pintype "passive+no_connect"))
    )
    (net (code "78") (name "unconnected-(IC46C-NC-Pad38)") (class "Default")
      (node (ref "IC46") (pin "38") (pinfunction "NC_38") (pintype "passive+no_connect"))
    )
    (net (code "79") (name "unconnected-(IC46C-NC-Pad39)") (class "Default")
      (node (ref "IC46") (pin "39") (pinfunction "NC_39") (pintype "passive+no_connect"))
    )
    (net (code "80") (name "unconnected-(IC46C-NC-Pad58)") (class "Default")
      (node (ref "IC46") (pin "58") (pinfunction "NC_58") (pintype "passive+no_connect"))
    )
    (net (code "81") (name "unconnected-(IC46C-NC-Pad59)") (class "Default")
      (node (ref "IC46") (pin "59") (pinfunction "NC_59") (pintype "passive+no_connect"))
    )
  )
)
